# RCSwitch_v1.net
KiCad netlist of a schematic drawn in EAGLE
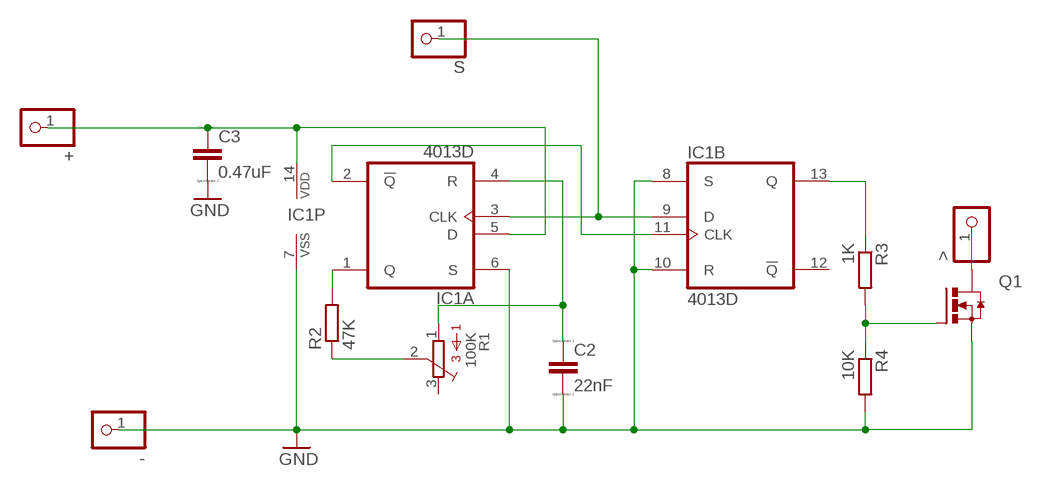
[diagram p0: schematic, sheet 1]

(export (version "E")
  (design (tool "Eeschema 10.0.6"))
  (components
    (comp (ref "+")
      (value "PINHD-1X1")
      (footprint "eagle-import:1X01")
      (libsource (lib "eagle-import") (part "PINHD-1X1"))
    )
    (comp (ref "-")
      (value "PINHD-1X1")
      (footprint "eagle-import:1X01")
      (libsource (lib "eagle-import") (part "PINHD-1X1"))
    )
    (comp (ref ">")
      (value "PINHD-1X1")
      (footprint "eagle-import:1X01")
      (libsource (lib "eagle-import") (part "PINHD-1X1"))
    )
    (comp (ref "C2")
      (value "22nF")
      (footprint "eagle-import:C3216")
      (libsource (lib "eagle-import") (part "CC3216"))
    )
    (comp (ref "C3")
      (value "0.47uF")
      (footprint "eagle-import:C3216")
      (libsource (lib "eagle-import") (part "CC3216"))
    )
    (comp (ref "IC1")
      (value "4013D")
      (footprint "eagle-import:SO14")
      (libsource (lib "eagle-import") (part "4013D"))
    )
    (comp (ref "Q1")
      (value "IRF3704S")
      (footprint "eagle-import:D2PACK")
      (libsource (lib "eagle-import") (part "IRF3704S"))
    )
    (comp (ref "R1")
      (value "100K")
      (footprint "eagle-import:3386P")
      (libsource (lib "eagle-import") (part "3386-P"))
    )
    (comp (ref "R2")
      (value "47K")
      (footprint "eagle-import:R3225")
      (libsource (lib "eagle-import") (part "R-EU_R3225"))
    )
    (comp (ref "R3")
      (value "1K")
      (footprint "eagle-import:R3225")
      (libsource (lib "eagle-import") (part "R-EU_R3225"))
    )
    (comp (ref "R4")
      (value "10K")
      (footprint "eagle-import:R3225")
      (libsource (lib "eagle-import") (part "R-EU_R3225"))
    )
    (comp (ref "S")
      (value "PINHD-1X1")
      (footprint "eagle-import:1X01")
      (libsource (lib "eagle-import") (part "PINHD-1X1"))
    )
  )
  (nets
    (net (code "1") (name "GND") (class "Default")
      (node (ref "-") (pin "1") (pinfunction "1_1") (pintype "passive"))
      (node (ref "C2") (pin "2") (pinfunction "2_2") (pintype "passive"))
      (node (ref "C3") (pin "2") (pinfunction "2_2") (pintype "passive"))
      (node (ref "IC1") (pin "10") (pinfunction "R_10") (pintype "input"))
      (node (ref "IC1") (pin "6") (pinfunction "S_6") (pintype "input"))
      (node (ref "IC1") (pin "7") (pinfunction "VSS_7") (pintype "power_in"))
      (node (ref "IC1") (pin "8") (pinfunction "S_8") (pintype "input"))
      (node (ref "Q1") (pin "3") (pinfunction "S_3") (pintype "passive"))
      (node (ref "R4") (pin "2") (pinfunction "2_2") (pintype "passive"))
    )
    (net (code "2") (name "Net-(IC1A-CLK)") (class "Default")
      (node (ref "IC1") (pin "3") (pinfunction "CLK_3") (pintype "input"))
      (node (ref "IC1") (pin "9") (pinfunction "D_9") (pintype "input"))
      (node (ref "S") (pin "1") (pinfunction "1_1") (pintype "passive"))
    )
    (net (code "3") (name "Net-(IC1A-D)") (class "Default")
      (node (ref "+") (pin "1") (pinfunction "1_1") (pintype "passive"))
      (node (ref "C3") (pin "1") (pinfunction "1_1") (pintype "passive"))
      (node (ref "IC1") (pin "14") (pinfunction "VDD_14") (pintype "power_in"))
      (node (ref "IC1") (pin "5") (pinfunction "D_5") (pintype "input"))
    )
    (net (code "4") (name "Net-(IC1A-Q)") (class "Default")
      (node (ref "IC1") (pin "1") (pinfunction "Q_1") (pintype "output"))
      (node (ref "R2") (pin "2") (pinfunction "2_2") (pintype "passive"))
    )
    (net (code "5") (name "Net-(IC1A-R)") (class "Default")
      (node (ref "C2") (pin "1") (pinfunction "1_1") (pintype "passive"))
      (node (ref "IC1") (pin "4") (pinfunction "R_4") (pintype "input"))
      (node (ref "R1") (pin "1") (pinfunction "1_1") (pintype "passive"))
    )
    (net (code "6") (name "Net-(IC1A-~{Q})") (class "Default")
      (node (ref "IC1") (pin "11") (pinfunction "CLK_11") (pintype "input"))
      (node (ref "IC1") (pin "2") (pinfunction "~{Q}_2") (pintype "output"))
    )
    (net (code "7") (name "Net-(IC1B-Q)") (class "Default")
      (node (ref "IC1") (pin "13") (pinfunction "Q_13") (pintype "output"))
      (node (ref "R3") (pin "1") (pinfunction "1_1") (pintype "passive"))
    )
    (net (code "8") (name "Net-(Q1-D)") (class "Default")
      (node (ref ">") (pin "1") (pinfunction "1_1") (pintype "passive"))
      (node (ref "Q1") (pin "2") (pinfunction "D_2") (pintype "passive"))
    )
    (net (code "9") (name "Net-(Q1-G)") (class "Default")
      (node (ref "Q1") (pin "1") (pinfunction "G_1") (pintype "passive"))
      (node (ref "R3") (pin "2") (pinfunction "2_2") (pintype "passive"))
      (node (ref "R4") (pin "1") (pinfunction "1_1") (pintype "passive"))
    )
    (net (code "10") (name "Net-(R1-Pad2)") (class "Default")
      (node (ref "R1") (pin "2") (pinfunction "2_2") (pintype "passive"))
      (node (ref "R2") (pin "1") (pinfunction "1_1") (pintype "passive"))
    )
    (net (code "11") (name "unconnected-(IC1B-~{Q}-Pad12)") (class "Default")
      (node (ref "IC1") (pin "12") (pinfunction "~{Q}_12") (pintype "output"))
    )
    (net (code "12") (name "unconnected-(R1-Pad3)") (class "Default")
      (node (ref "R1") (pin "3") (pinfunction "3_3") (pintype "passive"))
    )
  )
)
